# amebot_motors.net
KiCad netlist of a schematic drawn in EAGLE
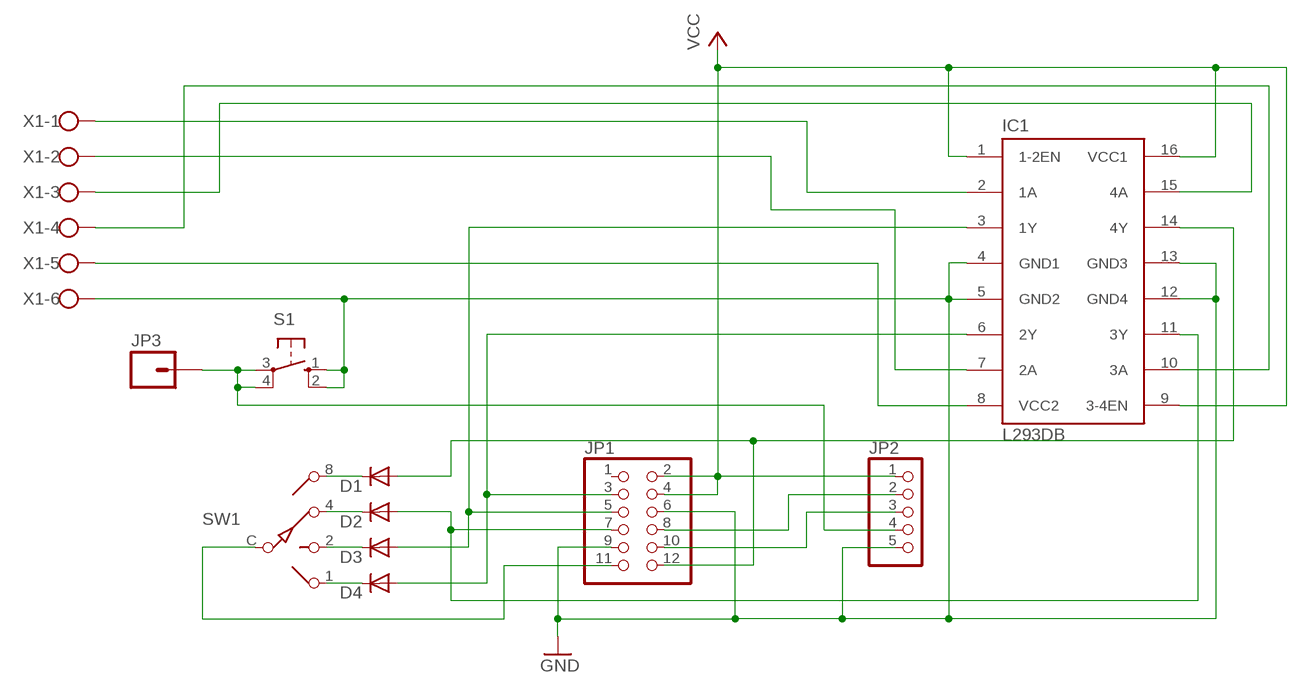
[diagram p0: schematic, sheet 1]

(export (version "E")
  (design (tool "Eeschema 10.0.6"))
  (components
    (comp (ref "D1")
      (value "DIODE-MICROMELF-W")
      (footprint "eagle-import:MICROMELF-W")
      (libsource (lib "eagle-import") (part "DIODE-MICROMELF-W"))
    )
    (comp (ref "D2")
      (value "DIODE-MICROMELF-W")
      (footprint "eagle-import:MICROMELF-W")
      (libsource (lib "eagle-import") (part "DIODE-MICROMELF-W"))
    )
    (comp (ref "D3")
      (value "DIODE-MICROMELF-W")
      (footprint "eagle-import:MICROMELF-W")
      (libsource (lib "eagle-import") (part "DIODE-MICROMELF-W"))
    )
    (comp (ref "D4")
      (value "DIODE-MICROMELF-W")
      (footprint "eagle-import:MICROMELF-W")
      (libsource (lib "eagle-import") (part "DIODE-MICROMELF-W"))
    )
    (comp (ref "IC1")
      (value "L293DB")
      (footprint "eagle-import:DIL16VAR")
      (libsource (lib "eagle-import") (part "L293DB"))
    )
    (comp (ref "JP1")
      (value "PINHD-2X6")
      (footprint "eagle-import:2X06")
      (libsource (lib "eagle-import") (part "PINHD-2X6"))
    )
    (comp (ref "JP2")
      (value "PINHD-1X5")
      (footprint "eagle-import:1X05")
      (libsource (lib "eagle-import") (part "PINHD-1X5"))
    )
    (comp (ref "JP3")
      (value "M01PTH_LONGPAD")
      (footprint "eagle-import:1X01_LONGPAD")
      (libsource (lib "eagle-import") (part "M01PTH_LONGPAD"))
    )
    (comp (ref "S1")
      (value "10-XX")
      (footprint "eagle-import:B3F-10XX")
      (fields (field (name "MPN") "B3F-1000"))
      (libsource (lib "eagle-import") (part "10-XX"))
    )
    (comp (ref "SW1")
      (value "SW-C10")
      (footprint "eagle-import:SW-C10")
      (libsource (lib "eagle-import") (part "SW-C10"))
    )
    (comp (ref "X1")
      (value "W237-6")
      (footprint "eagle-import:W237-6")
      (libsource (lib "eagle-import") (part "W237-6"))
    )
  )
  (nets
    (net (code "1") (name "GND") (class "Default")
      (node (ref "IC1") (pin "12") (pinfunction "GND4_12") (pintype "power_in"))
      (node (ref "IC1") (pin "13") (pinfunction "GND3_13") (pintype "power_in"))
      (node (ref "IC1") (pin "4") (pinfunction "GND1_4") (pintype "power_in"))
      (node (ref "IC1") (pin "5") (pinfunction "GND2_5") (pintype "power_in"))
      (node (ref "JP1") (pin "6") (pinfunction "6_6") (pintype "passive"))
      (node (ref "JP1") (pin "9") (pinfunction "9_9") (pintype "passive"))
      (node (ref "JP2") (pin "5") (pinfunction "5_5") (pintype "passive"))
      (node (ref "S1") (pin "1") (pinfunction "S_1") (pintype "passive"))
      (node (ref "S1") (pin "2") (pinfunction "S1_2") (pintype "passive"))
      (node (ref "X1") (pin "6") (pinfunction "KL_6") (pintype "passive"))
    )
    (net (code "2") (name "Net-(D1-PadC)") (class "Default")
      (node (ref "D1") (pin "C") (pinfunction "C_C") (pintype "passive"))
      (node (ref "SW1") (pin "8") (pinfunction "8_8") (pintype "passive"))
    )
    (net (code "3") (name "Net-(D2-PadC)") (class "Default")
      (node (ref "D2") (pin "C") (pinfunction "C_C") (pintype "passive"))
      (node (ref "SW1") (pin "4") (pinfunction "4_4") (pintype "passive"))
    )
    (net (code "4") (name "Net-(D3-PadC)") (class "Default")
      (node (ref "D3") (pin "C") (pinfunction "C_C") (pintype "passive"))
      (node (ref "SW1") (pin "2") (pinfunction "2_2") (pintype "passive"))
    )
    (net (code "5") (name "Net-(D4-PadC)") (class "Default")
      (node (ref "D4") (pin "C") (pinfunction "C_C") (pintype "passive"))
      (node (ref "SW1") (pin "1") (pinfunction "1_1") (pintype "passive"))
    )
    (net (code "6") (name "Net-(IC1-1A)") (class "Default")
      (node (ref "IC1") (pin "2") (pinfunction "1A_2") (pintype "input"))
      (node (ref "X1") (pin "1") (pinfunction "KL_1") (pintype "passive"))
    )
    (net (code "7") (name "Net-(IC1-1Y)") (class "Default")
      (node (ref "D3") (pin "A") (pinfunction "A_A") (pintype "passive"))
      (node (ref "IC1") (pin "3") (pinfunction "1Y_3") (pintype "output"))
      (node (ref "JP1") (pin "5") (pinfunction "5_5") (pintype "passive"))
    )
    (net (code "8") (name "Net-(IC1-2A)") (class "Default")
      (node (ref "IC1") (pin "7") (pinfunction "2A_7") (pintype "input"))
      (node (ref "X1") (pin "2") (pinfunction "KL_2") (pintype "passive"))
    )
    (net (code "9") (name "Net-(IC1-2Y)") (class "Default")
      (node (ref "D4") (pin "A") (pinfunction "A_A") (pintype "passive"))
      (node (ref "IC1") (pin "6") (pinfunction "2Y_6") (pintype "output"))
      (node (ref "JP1") (pin "3") (pinfunction "3_3") (pintype "passive"))
    )
    (net (code "10") (name "Net-(IC1-3A)") (class "Default")
      (node (ref "IC1") (pin "10") (pinfunction "3A_10") (pintype "input"))
      (node (ref "X1") (pin "4") (pinfunction "KL_4") (pintype "passive"))
    )
    (net (code "11") (name "Net-(IC1-3Y)") (class "Default")
      (node (ref "D2") (pin "A") (pinfunction "A_A") (pintype "passive"))
      (node (ref "IC1") (pin "11") (pinfunction "3Y_11") (pintype "output"))
      (node (ref "JP1") (pin "7") (pinfunction "7_7") (pintype "passive"))
    )
    (net (code "12") (name "Net-(IC1-4A)") (class "Default")
      (node (ref "IC1") (pin "15") (pinfunction "4A_15") (pintype "input"))
      (node (ref "X1") (pin "3") (pinfunction "KL_3") (pintype "passive"))
    )
    (net (code "13") (name "Net-(IC1-4Y)") (class "Default")
      (node (ref "D1") (pin "A") (pinfunction "A_A") (pintype "passive"))
      (node (ref "IC1") (pin "14") (pinfunction "4Y_14") (pintype "output"))
      (node (ref "JP1") (pin "12") (pinfunction "12_12") (pintype "passive"))
    )
    (net (code "14") (name "Net-(IC1-VCC2)") (class "Default")
      (node (ref "IC1") (pin "8") (pinfunction "VCC2_8") (pintype "power_in"))
      (node (ref "X1") (pin "5") (pinfunction "KL_5") (pintype "passive"))
    )
    (net (code "15") (name "Net-(JP1-Pad8)") (class "Default")
      (node (ref "JP1") (pin "8") (pinfunction "8_8") (pintype "passive"))
      (node (ref "JP2") (pin "2") (pinfunction "2_2") (pintype "passive"))
    )
    (net (code "16") (name "Net-(JP1-Pad10)") (class "Default")
      (node (ref "JP1") (pin "10") (pinfunction "10_10") (pintype "passive"))
      (node (ref "JP2") (pin "3") (pinfunction "3_3") (pintype "passive"))
    )
    (net (code "17") (name "Net-(JP1-Pad11)") (class "Default")
      (node (ref "JP1") (pin "11") (pinfunction "11_11") (pintype "passive"))
      (node (ref "SW1") (pin "C") (pinfunction "C_C") (pintype "passive"))
    )
    (net (code "18") (name "Net-(S1-P)") (class "Default")
      (node (ref "JP2") (pin "4") (pinfunction "4_4") (pintype "passive"))
      (node (ref "JP3") (pin "1") (pinfunction "1_1") (pintype "passive"))
      (node (ref "S1") (pin "3") (pinfunction "P_3") (pintype "passive"))
      (node (ref "S1") (pin "4") (pinfunction "P1_4") (pintype "passive"))
    )
    (net (code "19") (name "VCC") (class "Default")
      (node (ref "IC1") (pin "1") (pinfunction "1-2EN_1") (pintype "input"))
      (node (ref "IC1") (pin "16") (pinfunction "VCC1_16") (pintype "power_in"))
      (node (ref "IC1") (pin "9") (pinfunction "3-4EN_9") (pintype "input"))
      (node (ref "JP1") (pin "2") (pinfunction "2_2") (pintype "passive"))
      (node (ref "JP1") (pin "4") (pinfunction "4_4") (pintype "passive"))
      (node (ref "JP2") (pin "1") (pinfunction "1_1") (pintype "passive"))
    )
    (net (code "20") (name "unconnected-(JP1-Pad1)") (class "Default")
      (node (ref "JP1") (pin "1") (pinfunction "1_1") (pintype "passive"))
    )
  )
)
